# Power.net
KiCad netlist of a schematic drawn in Altium Designer
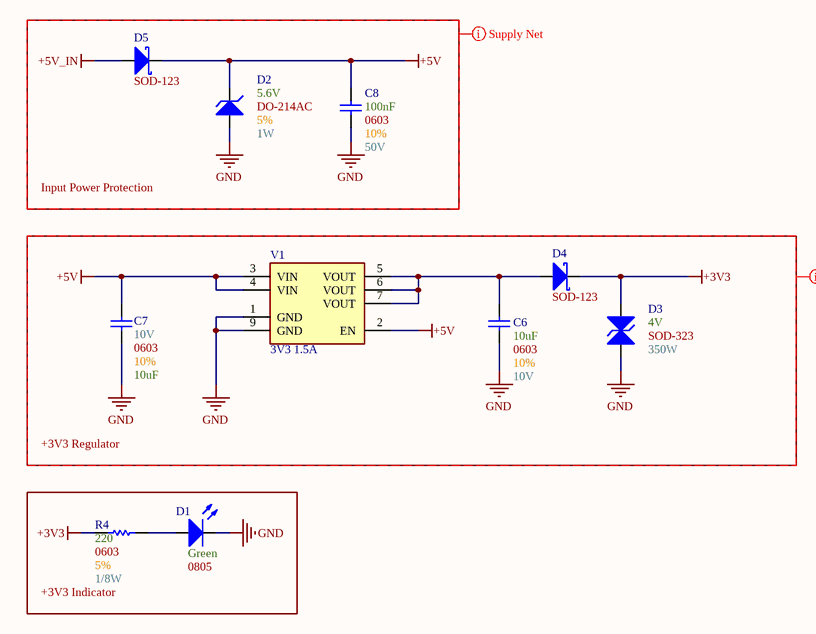
[diagram p0: Power.SchDoc]

(export (version "E")
  (design (tool "Eeschema 10.0.6"))
  (components
    (comp (ref "C6")
      (value "[Cap] 0603 10uF 10% 10V")
      (footprint "[Cap] SMD 0603")
      (description "CL10A106KP8NNNC")
      (fields
        (field (name "MAX VOLTAGE") "10V")
        (field (name "SIZE PACKAGE") "0603")
        (field (name "TOLERANCE") "10%")
        (field (name "CAPACITANCE") "10uF")
      )
      (libsource (lib "Capacitors") (part "[Cap] 0603 10uF 10% 10V"))
    )
    (comp (ref "C7")
      (value "[Cap] 0603 10uF 10% 10V")
      (footprint "[Cap] SMD 0603")
      (description "CL10A106KP8NNNC")
      (fields
        (field (name "MAX VOLTAGE") "10V")
        (field (name "SIZE PACKAGE") "0603")
        (field (name "TOLERANCE") "10%")
        (field (name "CAPACITANCE") "10uF")
      )
      (libsource (lib "Capacitors") (part "[Cap] 0603 10uF 10% 10V"))
    )
    (comp (ref "C8")
      (value "[Cap] 0603 0.1uF 10% 50V")
      (footprint "[Cap] SMD 0603")
      (description "CL10B104KB8NNNC")
      (fields
        (field (name "MAX VOLTAGE") "50V")
        (field (name "SIZE PACKAGE") "0603")
        (field (name "TOLERANCE") "10%")
        (field (name "CAPACITANCE") "100nF")
      )
      (libsource (lib "Capacitors") (part "[Cap] 0603 0.1uF 10% 50V"))
    )
    (comp (ref "D1")
      (value "[LED] SMD 0805 Green")
      (footprint "[LED] SMD 0805")
      (description "LG R971-KN-1-0-20-R18")
      (fields (field (name "COLOR") "Green") (field (name "SIZE PACKAGE") "0805"))
      (libsource (lib "LEDs") (part "[LED] SMD 0805 Green"))
    )
    (comp (ref "D2")
      (value "DO-214AC")
      (footprint "DO-214AC")
      (description "SMAZ5V6-13-F")
      (fields
        (field (name "TOLERANCE") "5%")
        (field (name "WATTAGE") "1W")
        (field (name "OPTIMAL ZENER VOLTAGE") "5.6V")
      )
      (libsource (lib "Diodes") (part "[Zener] SMD 5.6V 1W 5%"))
    )
    (comp (ref "D3")
      (value "SOD-323")
      (footprint "SOD-323")
      (description "CDSOD323-T03C")
      (fields (field (name "WATTAGE") "350W") (field (name "OPTIMAL ZENER VOLTAGE") "4V"))
      (libsource (lib "Diodes") (part "[TVS] 3.3Vnom 19Vclamp_max"))
    )
    (comp (ref "D4")
      (value "SOD123")
      (footprint "SOD-123")
      (description "B5819W-TP")
      (libsource (lib "Diodes") (part "[Schottky] SMD 40V 1A"))
    )
    (comp (ref "D5")
      (value "SOD123")
      (footprint "SOD-123")
      (description "B5819W-TP")
      (libsource (lib "Diodes") (part "[Schottky] SMD 40V 1A"))
    )
    (comp (ref "R4")
      (value "[220] SMD 0603 5% 1/10W")
      (footprint "[Res] SMD 0603")
      (description "RK73B1JTTD221J")
      (fields
        (field (name "WATTAGE") "1/8W")
        (field (name "TOLERANCE") "5%")
        (field (name "RESISTANCE") "220")
        (field (name "SIZE PACKAGE") "0603")
      )
      (libsource (lib "Resistors") (part "[220] SMD 0603 5% 1/10W"))
    )
    (comp (ref "V1")
      (value "3V3 1.5A")
      (footprint "[Linear] 3V3 1.5A")
      (description "AP7362A-33SP-13")
      (libsource (lib "Voltage Regulators") (part "[Linear] SMD 3V3 1.5A"))
    )
  )
  (nets
    (net (code "1") (name "+3V3") (class "Default")
      (node (ref "D3") (pin "1") (pinfunction "K_1") (pintype "passive"))
      (node (ref "D4") (pin "1") (pinfunction "K_1") (pintype "passive"))
      (node (ref "R4") (pin "1") (pinfunction "1_1") (pintype "passive"))
    )
    (net (code "2") (name "+5V") (class "Default")
      (node (ref "C7") (pin "2") (pinfunction "2_2") (pintype "passive"))
      (node (ref "C8") (pin "2") (pinfunction "2_2") (pintype "passive"))
      (node (ref "D2") (pin "1") (pinfunction "K_1") (pintype "passive"))
      (node (ref "D5") (pin "1") (pinfunction "K_1") (pintype "passive"))
      (node (ref "V1") (pin "2") (pinfunction "EN_2") (pintype "passive"))
      (node (ref "V1") (pin "3") (pinfunction "VIN_3") (pintype "passive"))
      (node (ref "V1") (pin "4") (pinfunction "VIN_4") (pintype "passive"))
    )
    (net (code "3") (name "+5V_IN") (class "Default")
      (node (ref "D5") (pin "2") (pinfunction "A_2") (pintype "passive"))
    )
    (net (code "4") (name "GND") (class "Default")
      (node (ref "C6") (pin "1") (pinfunction "1_1") (pintype "passive"))
      (node (ref "C7") (pin "1") (pinfunction "1_1") (pintype "passive"))
      (node (ref "C8") (pin "1") (pinfunction "1_1") (pintype "passive"))
      (node (ref "D1") (pin "2") (pinfunction "Cathode_2") (pintype "passive"))
      (node (ref "D2") (pin "2") (pinfunction "A_2") (pintype "passive"))
      (node (ref "D3") (pin "2") (pinfunction "A_2") (pintype "passive"))
      (node (ref "V1") (pin "1") (pinfunction "GND_1") (pintype "passive"))
      (node (ref "V1") (pin "9") (pinfunction "GND_9") (pintype "passive"))
    )
    (net (code "5") (name "Net-(D1-Anode)") (class "Default")
      (node (ref "D1") (pin "1") (pinfunction "Anode_1") (pintype "passive"))
      (node (ref "R4") (pin "2") (pinfunction "2_2") (pintype "passive"))
    )
    (net (code "6") (name "Net-(D4-A)") (class "Default")
      (node (ref "C6") (pin "2") (pinfunction "2_2") (pintype "passive"))
      (node (ref "D4") (pin "2") (pinfunction "A_2") (pintype "passive"))
      (node (ref "V1") (pin "5") (pinfunction "VOUT_5") (pintype "passive"))
      (node (ref "V1") (pin "6") (pinfunction "VOUT_6") (pintype "passive"))
      (node (ref "V1") (pin "7") (pinfunction "VOUT_7") (pintype "passive"))
    )
  )
)
